# SCH_LAIRR-Schematics_2026-06-09.net
KiCad netlist of a schematic drawn in EasyEDA
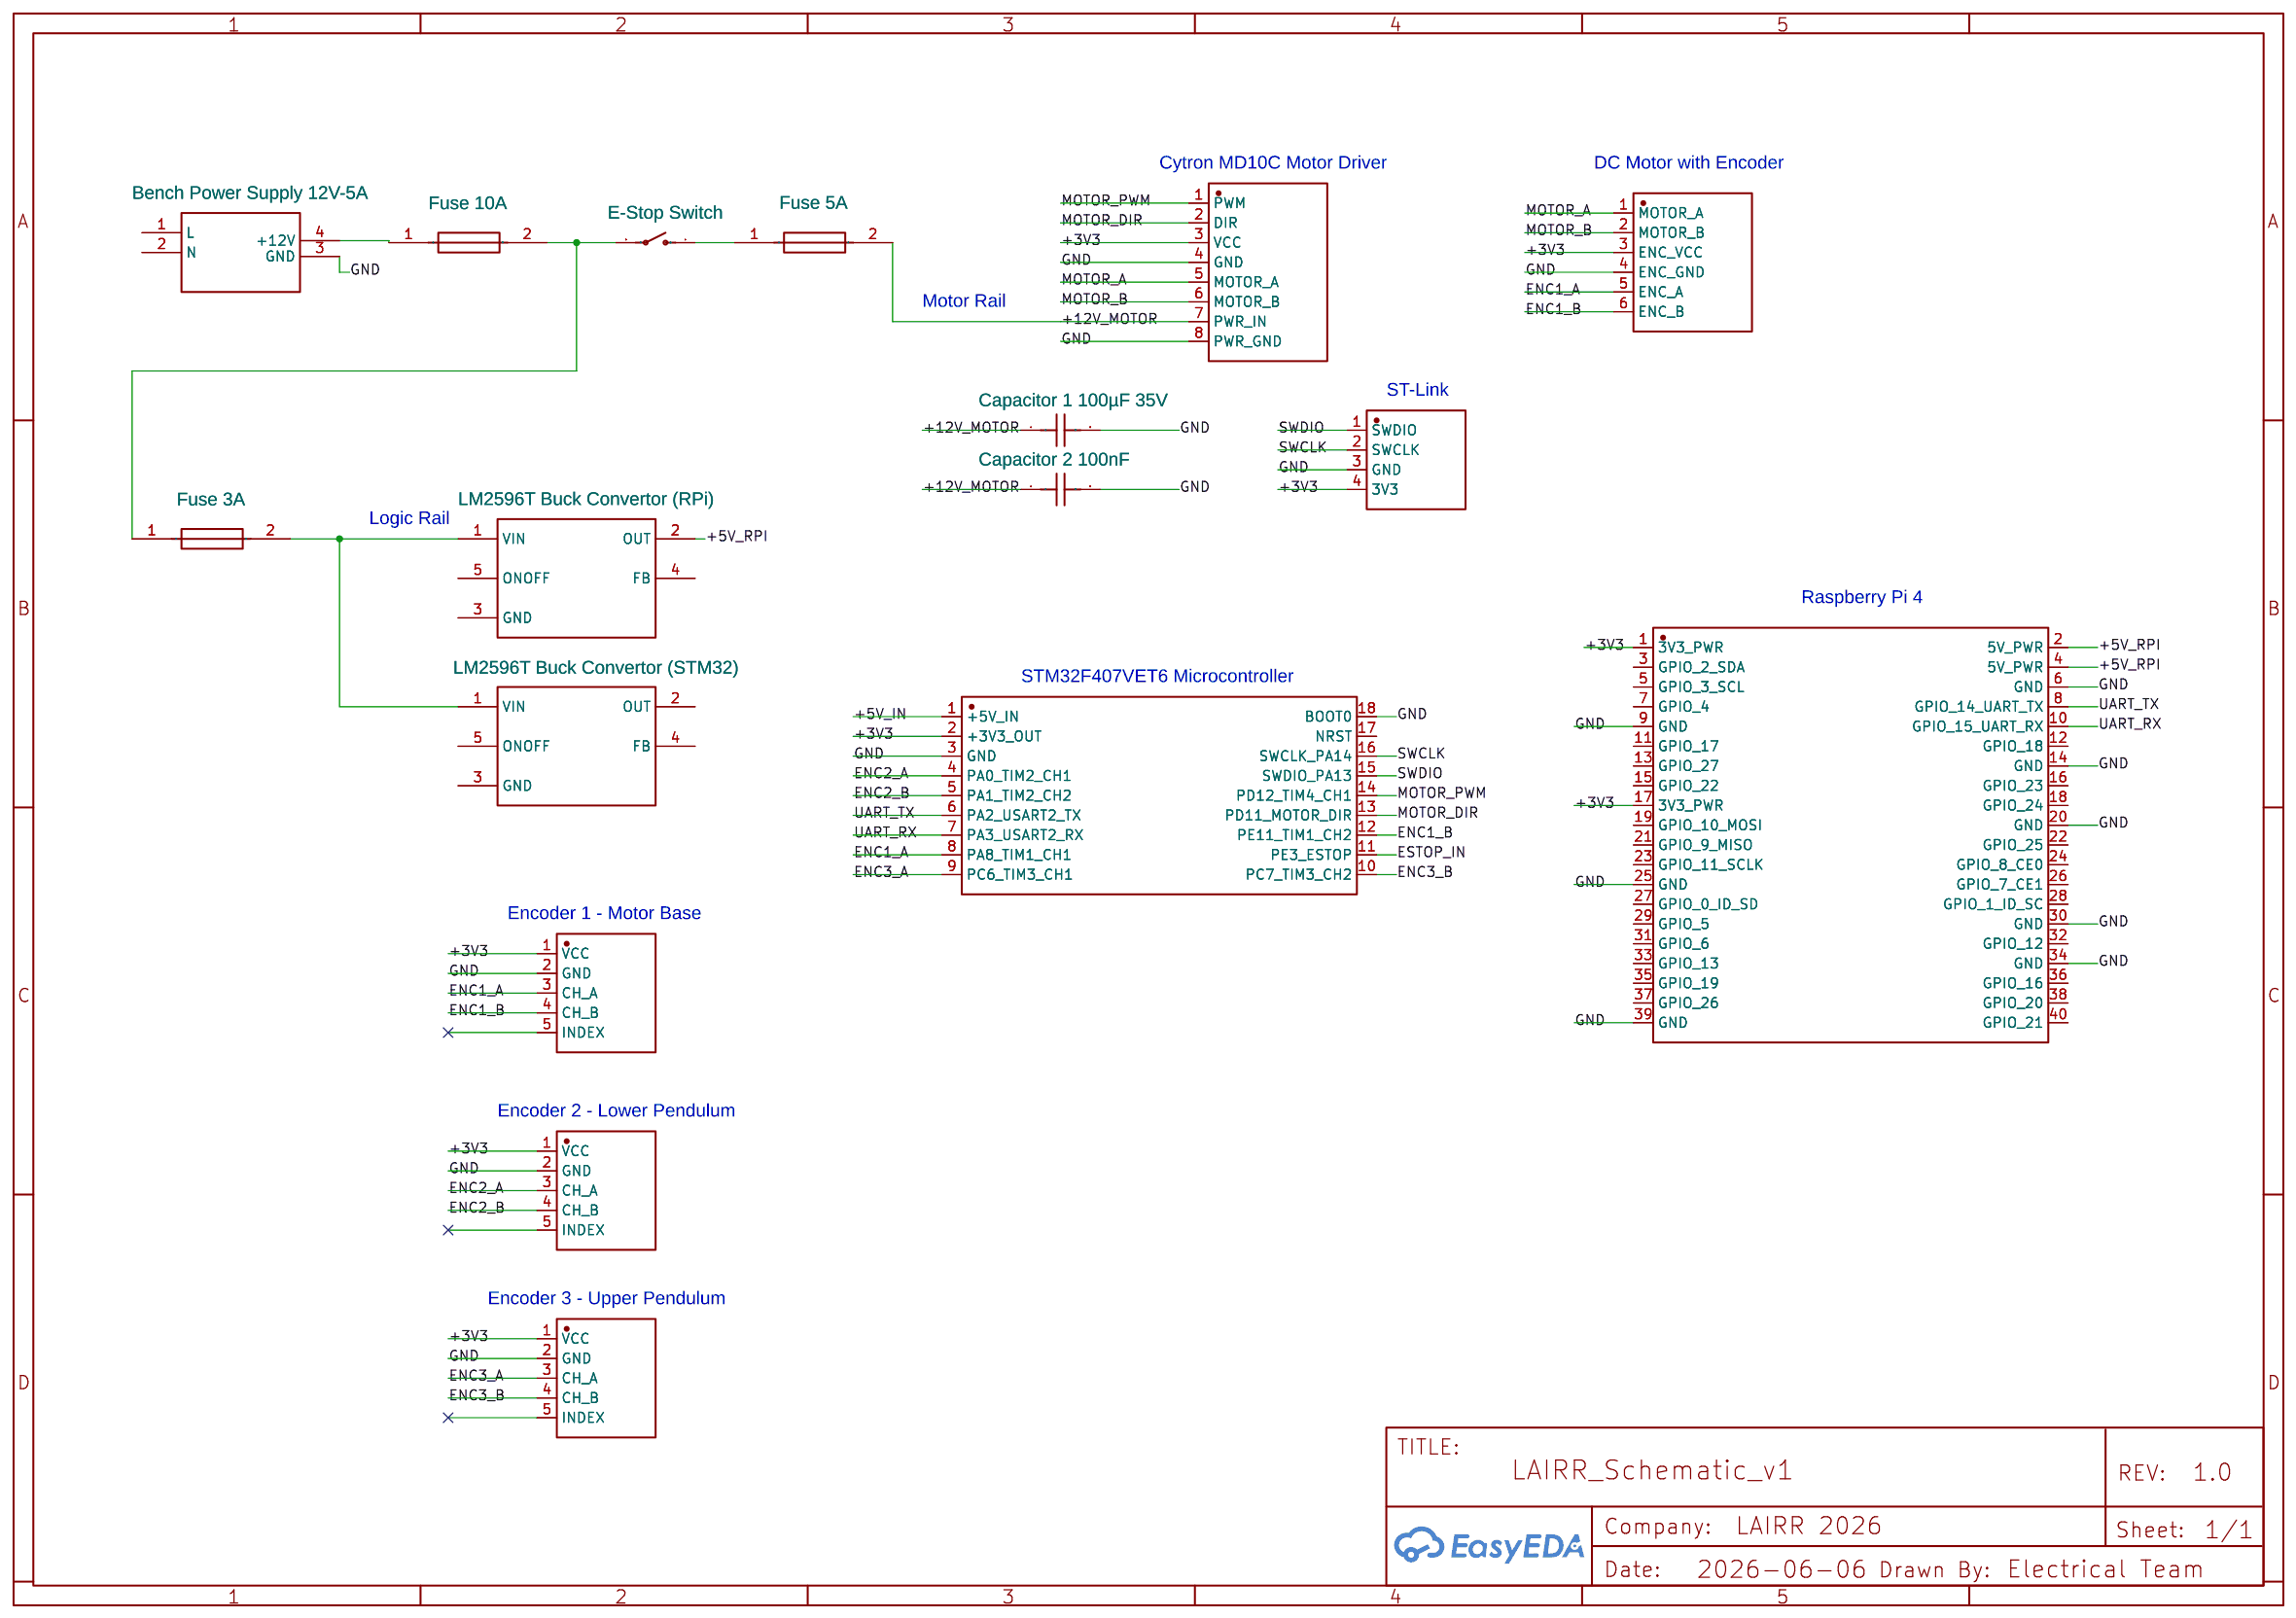
[diagram p0: schematic sheet]

(export (version "E")
  (design (tool "Eeschema 10.0.6"))
  (components
    (comp (ref "C1")
      (value "Capacitor 1 100µF 35V")
      (fields
        (field (name "Manufacturer Part") "101K/1KV Capacitor")
        (field (name "Manufacturer") "ReliaPro")
      )
      (libsource (lib "") (part "101K/1KV Capacitor"))
    )
    (comp (ref "C2")
      (value "Capacitor 2 100nF")
      (fields
        (field (name "Manufacturer Part") "101K/1KV Capacitor")
        (field (name "Manufacturer") "ReliaPro")
      )
      (libsource (lib "") (part "101K/1KV Capacitor"))
    )
    (comp (ref "D") (value "NO") (libsource (lib "") (part "Unknown_635_-675")))
    (comp (ref "PWR1") (value "Bench Power Supply 12V-5A") (libsource (lib "") (part "power-supply-12v-2a")))
    (comp (ref "U1")
      (value "Fuse 10A")
      (fields (field (name "Manufacturer Part") "汽车中号保险丝座"))
      (libsource (lib "") (part "FUSEE"))
    )
    (comp (ref "U2")
      (value "Fuse 5A")
      (fields (field (name "Manufacturer Part") "汽车中号保险丝座"))
      (libsource (lib "") (part "FUSEE"))
    )
    (comp (ref "U3")
      (value "Fuse 3A")
      (fields (field (name "Manufacturer Part") "汽车中号保险丝座"))
      (libsource (lib "") (part "FUSEE"))
    )
    (comp (ref "U4") (value "E-Stop Switch") (libsource (lib "") (part "SWITCH-SPST-2TV")))
    (comp (ref "U5") (value "LM2596T Buck Convertor (RPi)") (libsource (lib "") (part "LM2596T-12NOPB")))
    (comp (ref "U6") (value "LM2596T Buck Convertor (STM32)") (libsource (lib "") (part "LM2596T-12NOPB")))
    (comp (ref "U7") (value "NO") (libsource (lib "") (part "Unknown_850_-680")))
    (comp (ref "U8") (value "NO") (libsource (lib "") (part "Unknown_930_-390")))
    (comp (ref "U9") (value "NO") (libsource (lib "") (part "Unknown_300_-310")))
    (comp (ref "U10") (value "NO") (libsource (lib "") (part "Unknown_300_-210")))
    (comp (ref "U11") (value "NO") (libsource (lib "") (part "Unknown_580_-410")))
    (comp (ref "U12") (value "NO") (libsource (lib "") (part "Unknown_300_-115")))
    (comp (ref "U13") (value "NO") (libsource (lib "") (part "Unknown_710_-580")))
  )
  (nets
    (net (code "1") (name "/+3V3") (class "Default")
      (node (ref "D") (pin "3") (pinfunction "VCC_3") (pintype "unspecified"))
      (node (ref "U10") (pin "1") (pinfunction "VCC_1") (pintype "unspecified"))
      (node (ref "U11") (pin "2") (pinfunction "+3V3_OUT_2") (pintype "unspecified"))
      (node (ref "U12") (pin "1") (pinfunction "VCC_1") (pintype "unspecified"))
      (node (ref "U13") (pin "4") (pinfunction "3V3_4") (pintype "unspecified"))
      (node (ref "U7") (pin "3") (pinfunction "ENC_VCC_3") (pintype "unspecified"))
      (node (ref "U8") (pin "1") (pinfunction "3V3_PWR_1") (pintype "unspecified"))
      (node (ref "U8") (pin "17") (pinfunction "3V3_PWR_17") (pintype "unspecified"))
      (node (ref "U9") (pin "1") (pinfunction "VCC_1") (pintype "unspecified"))
    )
    (net (code "2") (name "/+5V_IN") (class "Default")
      (node (ref "U11") (pin "1") (pinfunction "+5V_IN_1") (pintype "unspecified"))
    )
    (net (code "3") (name "/+5V_RPI") (class "Default")
      (node (ref "U5") (pin "2") (pinfunction "OUT_2") (pintype "passive"))
      (node (ref "U8") (pin "2") (pinfunction "5V_PWR_2") (pintype "unspecified"))
      (node (ref "U8") (pin "4") (pinfunction "5V_PWR_4") (pintype "unspecified"))
    )
    (net (code "4") (name "/+12V_MOTOR") (class "Default")
      (node (ref "C1") (pin "1") (pinfunction "1_1") (pintype "unspecified"))
      (node (ref "C2") (pin "1") (pinfunction "1_1") (pintype "unspecified"))
      (node (ref "D") (pin "7") (pinfunction "PWR_IN_7") (pintype "unspecified"))
      (node (ref "U2") (pin "2") (pinfunction "2_2") (pintype "unspecified"))
    )
    (net (code "5") (name "/ENC1_A") (class "Default")
      (node (ref "U11") (pin "8") (pinfunction "PA8_TIM1_CH1_8") (pintype "unspecified"))
      (node (ref "U7") (pin "5") (pinfunction "ENC_A_5") (pintype "unspecified"))
      (node (ref "U9") (pin "3") (pinfunction "CH_A_3") (pintype "unspecified"))
    )
    (net (code "6") (name "/ENC1_B") (class "Default")
      (node (ref "U11") (pin "12") (pinfunction "PE11_TIM1_CH2_12") (pintype "unspecified"))
      (node (ref "U7") (pin "6") (pinfunction "ENC_B_6") (pintype "unspecified"))
      (node (ref "U9") (pin "4") (pinfunction "CH_B_4") (pintype "unspecified"))
    )
    (net (code "7") (name "/ENC2_A") (class "Default")
      (node (ref "U10") (pin "3") (pinfunction "CH_A_3") (pintype "unspecified"))
      (node (ref "U11") (pin "4") (pinfunction "PA0_TIM2_CH1_4") (pintype "unspecified"))
    )
    (net (code "8") (name "/ENC2_B") (class "Default")
      (node (ref "U10") (pin "4") (pinfunction "CH_B_4") (pintype "unspecified"))
      (node (ref "U11") (pin "5") (pinfunction "PA1_TIM2_CH2_5") (pintype "unspecified"))
    )
    (net (code "9") (name "/ENC3_A") (class "Default")
      (node (ref "U11") (pin "9") (pinfunction "PC6_TIM3_CH1_9") (pintype "unspecified"))
      (node (ref "U12") (pin "3") (pinfunction "CH_A_3") (pintype "unspecified"))
    )
    (net (code "10") (name "/ENC3_B") (class "Default")
      (node (ref "U11") (pin "10") (pinfunction "PC7_TIM3_CH2_10") (pintype "unspecified"))
      (node (ref "U12") (pin "4") (pinfunction "CH_B_4") (pintype "unspecified"))
    )
    (net (code "11") (name "/ESTOP_IN") (class "Default")
      (node (ref "U11") (pin "11") (pinfunction "PE3_ESTOP_11") (pintype "unspecified"))
    )
    (net (code "12") (name "/GND") (class "Default")
      (node (ref "C1") (pin "2") (pinfunction "2_2") (pintype "unspecified"))
      (node (ref "C2") (pin "2") (pinfunction "2_2") (pintype "unspecified"))
      (node (ref "D") (pin "4") (pinfunction "GND_4") (pintype "unspecified"))
      (node (ref "D") (pin "8") (pinfunction "PWR_GND_8") (pintype "unspecified"))
      (node (ref "PWR1") (pin "3") (pinfunction "GND_3") (pintype "unspecified"))
      (node (ref "U10") (pin "2") (pinfunction "GND_2") (pintype "unspecified"))
      (node (ref "U11") (pin "18") (pinfunction "BOOT0_18") (pintype "unspecified"))
      (node (ref "U11") (pin "3") (pinfunction "GND_3") (pintype "unspecified"))
      (node (ref "U12") (pin "2") (pinfunction "GND_2") (pintype "unspecified"))
      (node (ref "U13") (pin "3") (pinfunction "GND_3") (pintype "unspecified"))
      (node (ref "U7") (pin "4") (pinfunction "ENC_GND_4") (pintype "unspecified"))
      (node (ref "U8") (pin "14") (pinfunction "GND_14") (pintype "unspecified"))
      (node (ref "U8") (pin "20") (pinfunction "GND_20") (pintype "unspecified"))
      (node (ref "U8") (pin "25") (pinfunction "GND_25") (pintype "unspecified"))
      (node (ref "U8") (pin "30") (pinfunction "GND_30") (pintype "unspecified"))
      (node (ref "U8") (pin "34") (pinfunction "GND_34") (pintype "unspecified"))
      (node (ref "U8") (pin "39") (pinfunction "GND_39") (pintype "unspecified"))
      (node (ref "U8") (pin "6") (pinfunction "GND_6") (pintype "unspecified"))
      (node (ref "U8") (pin "9") (pinfunction "GND_9") (pintype "unspecified"))
      (node (ref "U9") (pin "2") (pinfunction "GND_2") (pintype "unspecified"))
    )
    (net (code "13") (name "/MOTOR_A") (class "Default")
      (node (ref "D") (pin "5") (pinfunction "MOTOR_A_5") (pintype "unspecified"))
      (node (ref "U7") (pin "1") (pinfunction "MOTOR_A_1") (pintype "unspecified"))
    )
    (net (code "14") (name "/MOTOR_B") (class "Default")
      (node (ref "D") (pin "6") (pinfunction "MOTOR_B_6") (pintype "unspecified"))
      (node (ref "U7") (pin "2") (pinfunction "MOTOR_B_2") (pintype "unspecified"))
    )
    (net (code "15") (name "/MOTOR_DIR") (class "Default")
      (node (ref "D") (pin "2") (pinfunction "DIR_2") (pintype "unspecified"))
      (node (ref "U11") (pin "13") (pinfunction "PD11_MOTOR_DIR_13") (pintype "unspecified"))
    )
    (net (code "16") (name "/MOTOR_PWM") (class "Default")
      (node (ref "D") (pin "1") (pinfunction "PWM_1") (pintype "unspecified"))
      (node (ref "U11") (pin "14") (pinfunction "PD12_TIM4_CH1_14") (pintype "unspecified"))
    )
    (net (code "17") (name "/SWCLK") (class "Default")
      (node (ref "U11") (pin "16") (pinfunction "SWCLK_PA14_16") (pintype "unspecified"))
      (node (ref "U13") (pin "2") (pinfunction "SWCLK_2") (pintype "unspecified"))
    )
    (net (code "18") (name "/SWDIO") (class "Default")
      (node (ref "U11") (pin "15") (pinfunction "SWDIO_PA13_15") (pintype "unspecified"))
      (node (ref "U13") (pin "1") (pinfunction "SWDIO_1") (pintype "unspecified"))
    )
    (net (code "19") (name "/UART_RX") (class "Default")
      (node (ref "U11") (pin "7") (pinfunction "PA3_USART2_RX_7") (pintype "unspecified"))
      (node (ref "U8") (pin "10") (pinfunction "GPIO_15_UART_RX_10") (pintype "unspecified"))
    )
    (net (code "20") (name "/UART_TX") (class "Default")
      (node (ref "U11") (pin "6") (pinfunction "PA2_USART2_TX_6") (pintype "unspecified"))
      (node (ref "U8") (pin "8") (pinfunction "GPIO_14_UART_TX_8") (pintype "unspecified"))
    )
    (net (code "21") (name "Net-(PWR1-+12V)") (class "Default")
      (node (ref "PWR1") (pin "4") (pinfunction "+12V_4") (pintype "unspecified"))
      (node (ref "U1") (pin "1") (pinfunction "1_1") (pintype "unspecified"))
    )
    (net (code "22") (name "Net-(U4-O)") (class "Default")
      (node (ref "U2") (pin "1") (pinfunction "1_1") (pintype "unspecified"))
      (node (ref "U4") (pin "1") (pinfunction "O_1") (pintype "unspecified"))
    )
    (net (code "23") (name "Net-(U4-P)") (class "Default")
      (node (ref "U1") (pin "2") (pinfunction "2_2") (pintype "unspecified"))
      (node (ref "U3") (pin "1") (pinfunction "1_1") (pintype "unspecified"))
      (node (ref "U4") (pin "2") (pinfunction "P_2") (pintype "unspecified"))
    )
    (net (code "24") (name "Net-(U5-VIN)") (class "Default")
      (node (ref "U3") (pin "2") (pinfunction "2_2") (pintype "unspecified"))
      (node (ref "U5") (pin "1") (pinfunction "VIN_1") (pintype "passive"))
      (node (ref "U6") (pin "1") (pinfunction "VIN_1") (pintype "passive"))
    )
    (net (code "25") (name "unconnected-(PWR1-L-Pad1)") (class "Default")
      (node (ref "PWR1") (pin "1") (pinfunction "L_1") (pintype "unspecified"))
    )
    (net (code "26") (name "unconnected-(PWR1-N-Pad2)") (class "Default")
      (node (ref "PWR1") (pin "2") (pinfunction "N_2") (pintype "unspecified"))
    )
    (net (code "27") (name "unconnected-(U5-FB-Pad4)") (class "Default")
      (node (ref "U5") (pin "4") (pinfunction "FB_4") (pintype "unspecified"))
    )
    (net (code "28") (name "unconnected-(U5-GND-Pad3)") (class "Default")
      (node (ref "U5") (pin "3") (pinfunction "GND_3") (pintype "passive"))
    )
    (net (code "29") (name "unconnected-(U5-ONOFF-Pad5)") (class "Default")
      (node (ref "U5") (pin "5") (pinfunction "ONOFF_5") (pintype "unspecified"))
    )
    (net (code "30") (name "unconnected-(U6-FB-Pad4)") (class "Default")
      (node (ref "U6") (pin "4") (pinfunction "FB_4") (pintype "unspecified"))
    )
    (net (code "31") (name "unconnected-(U6-GND-Pad3)") (class "Default")
      (node (ref "U6") (pin "3") (pinfunction "GND_3") (pintype "passive"))
    )
    (net (code "32") (name "unconnected-(U6-ONOFF-Pad5)") (class "Default")
      (node (ref "U6") (pin "5") (pinfunction "ONOFF_5") (pintype "unspecified"))
    )
    (net (code "33") (name "unconnected-(U6-OUT-Pad2)") (class "Default")
      (node (ref "U6") (pin "2") (pinfunction "OUT_2") (pintype "passive"))
    )
    (net (code "34") (name "unconnected-(U8-GPIO_0_ID_SD-Pad27)") (class "Default")
      (node (ref "U8") (pin "27") (pinfunction "GPIO_0_ID_SD_27") (pintype "unspecified"))
    )
    (net (code "35") (name "unconnected-(U8-GPIO_1_ID_SC-Pad28)") (class "Default")
      (node (ref "U8") (pin "28") (pinfunction "GPIO_1_ID_SC_28") (pintype "unspecified"))
    )
    (net (code "36") (name "unconnected-(U8-GPIO_2_SDA-Pad3)") (class "Default")
      (node (ref "U8") (pin "3") (pinfunction "GPIO_2_SDA_3") (pintype "unspecified"))
    )
    (net (code "37") (name "unconnected-(U8-GPIO_3_SCL-Pad5)") (class "Default")
      (node (ref "U8") (pin "5") (pinfunction "GPIO_3_SCL_5") (pintype "unspecified"))
    )
    (net (code "38") (name "unconnected-(U8-GPIO_4-Pad7)") (class "Default")
      (node (ref "U8") (pin "7") (pinfunction "GPIO_4_7") (pintype "unspecified"))
    )
    (net (code "39") (name "unconnected-(U8-GPIO_5-Pad29)") (class "Default")
      (node (ref "U8") (pin "29") (pinfunction "GPIO_5_29") (pintype "unspecified"))
    )
    (net (code "40") (name "unconnected-(U8-GPIO_6-Pad31)") (class "Default")
      (node (ref "U8") (pin "31") (pinfunction "GPIO_6_31") (pintype "unspecified"))
    )
    (net (code "41") (name "unconnected-(U8-GPIO_7_CE1-Pad26)") (class "Default")
      (node (ref "U8") (pin "26") (pinfunction "GPIO_7_CE1_26") (pintype "unspecified"))
    )
    (net (code "42") (name "unconnected-(U8-GPIO_8_CE0-Pad24)") (class "Default")
      (node (ref "U8") (pin "24") (pinfunction "GPIO_8_CE0_24") (pintype "unspecified"))
    )
    (net (code "43") (name "unconnected-(U8-GPIO_9_MISO-Pad21)") (class "Default")
      (node (ref "U8") (pin "21") (pinfunction "GPIO_9_MISO_21") (pintype "unspecified"))
    )
    (net (code "44") (name "unconnected-(U8-GPIO_10_MOSI-Pad19)") (class "Default")
      (node (ref "U8") (pin "19") (pinfunction "GPIO_10_MOSI_19") (pintype "unspecified"))
    )
    (net (code "45") (name "unconnected-(U8-GPIO_11_SCLK-Pad23)") (class "Default")
      (node (ref "U8") (pin "23") (pinfunction "GPIO_11_SCLK_23") (pintype "unspecified"))
    )
    (net (code "46") (name "unconnected-(U8-GPIO_12-Pad32)") (class "Default")
      (node (ref "U8") (pin "32") (pinfunction "GPIO_12_32") (pintype "unspecified"))
    )
    (net (code "47") (name "unconnected-(U8-GPIO_13-Pad33)") (class "Default")
      (node (ref "U8") (pin "33") (pinfunction "GPIO_13_33") (pintype "unspecified"))
    )
    (net (code "48") (name "unconnected-(U8-GPIO_16-Pad36)") (class "Default")
      (node (ref "U8") (pin "36") (pinfunction "GPIO_16_36") (pintype "unspecified"))
    )
    (net (code "49") (name "unconnected-(U8-GPIO_17-Pad11)") (class "Default")
      (node (ref "U8") (pin "11") (pinfunction "GPIO_17_11") (pintype "unspecified"))
    )
    (net (code "50") (name "unconnected-(U8-GPIO_18-Pad12)") (class "Default")
      (node (ref "U8") (pin "12") (pinfunction "GPIO_18_12") (pintype "unspecified"))
    )
    (net (code "51") (name "unconnected-(U8-GPIO_19-Pad35)") (class "Default")
      (node (ref "U8") (pin "35") (pinfunction "GPIO_19_35") (pintype "unspecified"))
    )
    (net (code "52") (name "unconnected-(U8-GPIO_20-Pad38)") (class "Default")
      (node (ref "U8") (pin "38") (pinfunction "GPIO_20_38") (pintype "unspecified"))
    )
    (net (code "53") (name "unconnected-(U8-GPIO_21-Pad40)") (class "Default")
      (node (ref "U8") (pin "40") (pinfunction "GPIO_21_40") (pintype "unspecified"))
    )
    (net (code "54") (name "unconnected-(U8-GPIO_22-Pad15)") (class "Default")
      (node (ref "U8") (pin "15") (pinfunction "GPIO_22_15") (pintype "unspecified"))
    )
    (net (code "55") (name "unconnected-(U8-GPIO_23-Pad16)") (class "Default")
      (node (ref "U8") (pin "16") (pinfunction "GPIO_23_16") (pintype "unspecified"))
    )
    (net (code "56") (name "unconnected-(U8-GPIO_24-Pad18)") (class "Default")
      (node (ref "U8") (pin "18") (pinfunction "GPIO_24_18") (pintype "unspecified"))
    )
    (net (code "57") (name "unconnected-(U8-GPIO_25-Pad22)") (class "Default")
      (node (ref "U8") (pin "22") (pinfunction "GPIO_25_22") (pintype "unspecified"))
    )
    (net (code "58") (name "unconnected-(U8-GPIO_26-Pad37)") (class "Default")
      (node (ref "U8") (pin "37") (pinfunction "GPIO_26_37") (pintype "unspecified"))
    )
    (net (code "59") (name "unconnected-(U8-GPIO_27-Pad13)") (class "Default")
      (node (ref "U8") (pin "13") (pinfunction "GPIO_27_13") (pintype "unspecified"))
    )
    (net (code "60") (name "unconnected-(U9-INDEX-Pad5)") (class "Default")
      (node (ref "U9") (pin "5") (pinfunction "INDEX_5") (pintype "unspecified+no_connect"))
    )
    (net (code "61") (name "unconnected-(U10-INDEX-Pad5)") (class "Default")
      (node (ref "U10") (pin "5") (pinfunction "INDEX_5") (pintype "unspecified+no_connect"))
    )
    (net (code "62") (name "unconnected-(U11-NRST-Pad17)") (class "Default")
      (node (ref "U11") (pin "17") (pinfunction "NRST_17") (pintype "unspecified"))
    )
    (net (code "63") (name "unconnected-(U12-INDEX-Pad5)") (class "Default")
      (node (ref "U12") (pin "5") (pinfunction "INDEX_5") (pintype "unspecified+no_connect"))
    )
  )
)
